# V1_0.net
KiCad netlist of a schematic drawn in Altium Designer
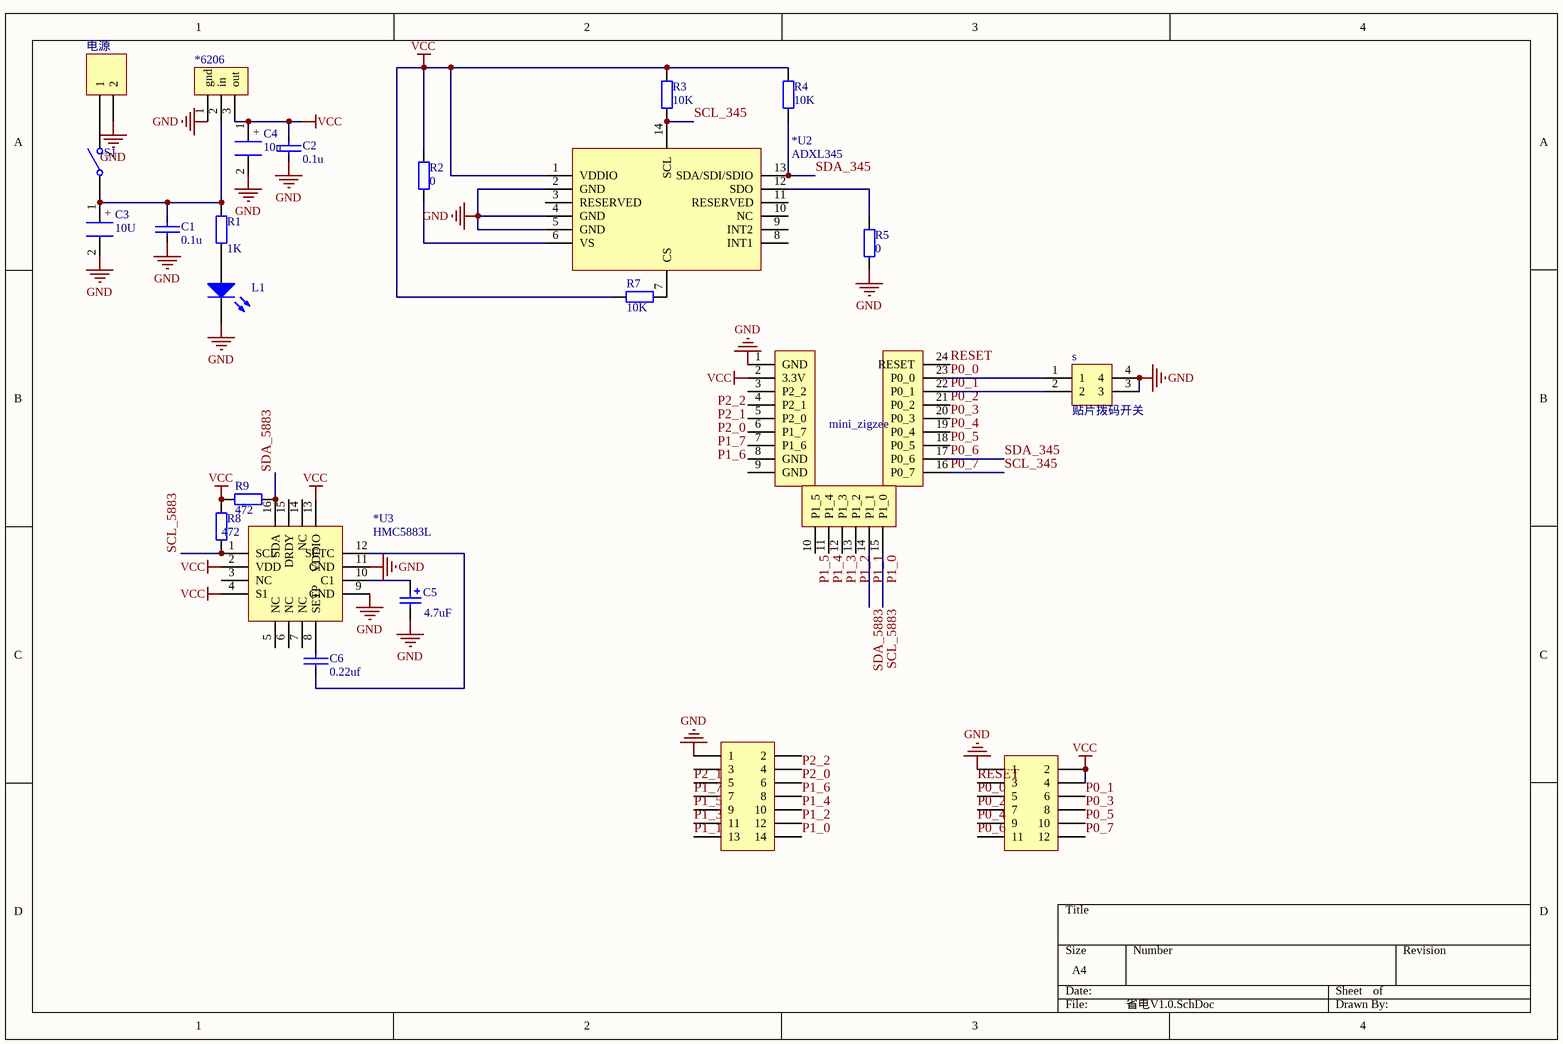
[diagram p0: 省电V1.0.SchDoc]

(export (version "E")
  (design (tool "Eeschema 10.0.6"))
  (components
    (comp (ref "*U1") (value "*6206") (footprint "SOT89/X.7") (libsource (lib "*") (part "6206A")))
    (comp (ref "*U2") (value "ADXL345") (footprint "ADXL345") (libsource (lib "Schlib1") (part "ADXL345")))
    (comp (ref "*U3") (value "HMC5883L") (footprint "HMC5883L") (libsource (lib "*") (part "HMC5883L")))
    (comp (ref "*U4")
      (value "mini_zigzee")
      (footprint "mini_zigbee")
      (libsource (lib "*") (part "mini_zigzee"))
    )
    (comp (ref "C1") (value "0.1u") (footprint "0603") (libsource (lib "hecheng") (part "CAP")))
    (comp (ref "C2") (value "0.1u") (footprint "0603") (libsource (lib "hecheng") (part "CAP")))
    (comp (ref "C3") (value "10U") (footprint "1206") (libsource (lib "hecheng") (part "CAP-10U-T")))
    (comp (ref "C4") (value "10u") (footprint "1206") (libsource (lib "hecheng") (part "CAP-10U-T")))
    (comp (ref "C5")
      (value "4.7uF")
      (footprint "0603")
      (description "Polarized Capacitor (Axial)")
      (fields
        (field (name "MANUFACTURER") "Generic Components")
        (field (name "Comment") "Cap Pol2")
        (field (name "PUBLISHER") "Altium Hobart Technology Centre")
      )
      (libsource (lib "hecheng") (part "Cap Pol2"))
    )
    (comp (ref "C6") (value "0.22uf") (footprint "0603") (libsource (lib "hecheng") (part "CAP")))
    (comp (ref "JP2")
      (value "Header 2X7")
      (footprint "HDR2-7")
      (description "Header, 7-Pin, Dual row")
      (fields (field (name "MANUFACTURER") "Generic Components"))
      (libsource (lib "hecheng") (part "Header 2X7"))
    )
    (comp (ref "JP3")
      (value "Header 2X6")
      (footprint "HDR2-6")
      (description "Header, 6-Pin, Dual row")
      (fields (field (name "MANUFACTURER") "Generic Components"))
      (libsource (lib "hecheng") (part "Header 2X6"))
    )
    (comp (ref "L1") (value "LED-3MM") (footprint "0603") (libsource (lib "hecheng") (part "LED-3MM")))
    (comp (ref "R1")
      (value "1K")
      (footprint "0603")
      (description "Resistor")
      (fields
        (field (name "MANUFACTURER") "Generic Components")
        (field (name "Comment") "Res")
        (field (name "PUBLISHER") "Altium Hobart Technology Centre")
      )
      (libsource (lib "hecheng") (part "Res"))
    )
    (comp (ref "R2")
      (value "0")
      (footprint "0603")
      (description "Resistor")
      (fields
        (field (name "MANUFACTURER") "Generic Components")
        (field (name "Comment") "Res")
        (field (name "PUBLISHER") "Altium Hobart Technology Centre")
      )
      (libsource (lib "hecheng") (part "Res"))
    )
    (comp (ref "R3")
      (value "10K")
      (footprint "0603")
      (description "Resistor")
      (fields
        (field (name "MANUFACTURER") "Generic Components")
        (field (name "Comment") "Res")
        (field (name "PUBLISHER") "Altium Hobart Technology Centre")
      )
      (libsource (lib "hecheng") (part "Res"))
    )
    (comp (ref "R4")
      (value "10K")
      (footprint "0603")
      (description "Resistor")
      (fields
        (field (name "MANUFACTURER") "Generic Components")
        (field (name "Comment") "Res")
        (field (name "PUBLISHER") "Altium Hobart Technology Centre")
      )
      (libsource (lib "hecheng") (part "Res"))
    )
    (comp (ref "R5")
      (value "0")
      (footprint "0603")
      (description "Resistor")
      (fields
        (field (name "MANUFACTURER") "Generic Components")
        (field (name "Comment") "Res")
        (field (name "PUBLISHER") "Altium Hobart Technology Centre")
      )
      (libsource (lib "hecheng") (part "Res"))
    )
    (comp (ref "R7")
      (value "10K")
      (footprint "0603")
      (description "Resistor")
      (fields
        (field (name "MANUFACTURER") "Generic Components")
        (field (name "Comment") "Res")
        (field (name "PUBLISHER") "Altium Hobart Technology Centre")
      )
      (libsource (lib "") (part "Res_1"))
    )
    (comp (ref "R8")
      (value "472")
      (footprint "0603")
      (description "Resistor")
      (fields
        (field (name "MANUFACTURER") "Generic Components")
        (field (name "Comment") "Res")
        (field (name "PUBLISHER") "Altium Hobart Technology Centre")
      )
      (libsource (lib "hecheng") (part "Res"))
    )
    (comp (ref "R9")
      (value "472")
      (footprint "0603")
      (description "Resistor")
      (fields
        (field (name "MANUFACTURER") "Generic Components")
        (field (name "Comment") "Res")
        (field (name "PUBLISHER") "Altium Hobart Technology Centre")
      )
      (libsource (lib "") (part "Res_1"))
    )
    (comp (ref "s") (value "贴片拨码开关") (footprint "贴片拨码开关") (libsource (lib "*") (part "贴片拨码开关")))
    (comp (ref "S1")
      (value "~")
      (footprint "手电筒开关")
      (description "Single-Pole, Single-Throw Switch")
      (fields (field (name "MANUFACTURER") "Generic Components"))
      (libsource (lib "hecheng") (part "SW-SPST"))
    )
    (comp (ref "电源")
      (value "Header 2")
      (footprint "2032纽扣底座")
      (description "Header, 2-Pin")
      (fields (field (name "PUBLISHER") "Altium Limited"))
      (libsource (lib "hecheng") (part "Header 2"))
    )
  )
  (nets
    (net (code "1") (name "/P0_0") (class "Default")
      (node (ref "*U4") (pin "23") (pinfunction "P0_0_23") (pintype "passive"))
      (node (ref "JP3") (pin "5") (pinfunction "5_5") (pintype "passive"))
      (node (ref "s") (pin "1") (pinfunction "1_1") (pintype "passive"))
    )
    (net (code "2") (name "/P0_1") (class "Default")
      (node (ref "*U4") (pin "22") (pinfunction "P0_1_22") (pintype "passive"))
      (node (ref "JP3") (pin "6") (pinfunction "6_6") (pintype "passive"))
      (node (ref "s") (pin "2") (pinfunction "2_2") (pintype "passive"))
    )
    (net (code "3") (name "/P0_2") (class "Default")
      (node (ref "*U4") (pin "21") (pinfunction "P0_2_21") (pintype "passive"))
      (node (ref "JP3") (pin "7") (pinfunction "7_7") (pintype "passive"))
    )
    (net (code "4") (name "/P0_3") (class "Default")
      (node (ref "*U4") (pin "20") (pinfunction "P0_3_20") (pintype "passive"))
      (node (ref "JP3") (pin "8") (pinfunction "8_8") (pintype "passive"))
    )
    (net (code "5") (name "/P0_4") (class "Default")
      (node (ref "*U4") (pin "19") (pinfunction "P0_4_19") (pintype "passive"))
      (node (ref "JP3") (pin "9") (pinfunction "9_9") (pintype "passive"))
    )
    (net (code "6") (name "/P0_5") (class "Default")
      (node (ref "*U4") (pin "18") (pinfunction "P0_5_18") (pintype "passive"))
      (node (ref "JP3") (pin "10") (pinfunction "10_10") (pintype "passive"))
    )
    (net (code "7") (name "/P0_6") (class "Default")
      (node (ref "*U2") (pin "13") (pinfunction "SDA/SDI/SDIO_13") (pintype "passive"))
      (node (ref "*U4") (pin "17") (pinfunction "P0_6_17") (pintype "passive"))
      (node (ref "JP3") (pin "11") (pinfunction "11_11") (pintype "passive"))
      (node (ref "R4") (pin "1") (pinfunction "1_1") (pintype "passive"))
    )
    (net (code "8") (name "/P0_7") (class "Default")
      (node (ref "*U2") (pin "14") (pinfunction "SCL_14") (pintype "passive"))
      (node (ref "*U4") (pin "16") (pinfunction "P0_7_16") (pintype "passive"))
      (node (ref "JP3") (pin "12") (pinfunction "12_12") (pintype "passive"))
      (node (ref "R3") (pin "1") (pinfunction "1_1") (pintype "passive"))
    )
    (net (code "9") (name "/P1_0") (class "Default")
      (node (ref "*U3") (pin "1") (pinfunction "SCL_1") (pintype "passive"))
      (node (ref "*U4") (pin "15") (pinfunction "P1_0_15") (pintype "passive"))
      (node (ref "JP2") (pin "14") (pinfunction "14_14") (pintype "passive"))
      (node (ref "R8") (pin "1") (pinfunction "1_1") (pintype "passive"))
    )
    (net (code "10") (name "/P1_1") (class "Default")
      (node (ref "*U3") (pin "16") (pinfunction "SDA_16") (pintype "passive"))
      (node (ref "*U4") (pin "14") (pinfunction "P1_1_14") (pintype "passive"))
      (node (ref "JP2") (pin "13") (pinfunction "13_13") (pintype "passive"))
      (node (ref "R9") (pin "1") (pinfunction "1_1") (pintype "passive"))
    )
    (net (code "11") (name "/P1_2") (class "Default")
      (node (ref "*U4") (pin "13") (pinfunction "P1_2_13") (pintype "passive"))
      (node (ref "JP2") (pin "12") (pinfunction "12_12") (pintype "passive"))
    )
    (net (code "12") (name "/P1_3") (class "Default")
      (node (ref "*U4") (pin "12") (pinfunction "P1_3_12") (pintype "passive"))
      (node (ref "JP2") (pin "11") (pinfunction "11_11") (pintype "passive"))
    )
    (net (code "13") (name "/P1_4") (class "Default")
      (node (ref "*U4") (pin "11") (pinfunction "P1_4_11") (pintype "passive"))
      (node (ref "JP2") (pin "10") (pinfunction "10_10") (pintype "passive"))
    )
    (net (code "14") (name "/P1_5") (class "Default")
      (node (ref "*U4") (pin "10") (pinfunction "P1_5_10") (pintype "passive"))
      (node (ref "JP2") (pin "9") (pinfunction "9_9") (pintype "passive"))
    )
    (net (code "15") (name "/P1_6") (class "Default")
      (node (ref "*U4") (pin "7") (pinfunction "P1_6_7") (pintype "passive"))
      (node (ref "JP2") (pin "8") (pinfunction "8_8") (pintype "passive"))
    )
    (net (code "16") (name "/P1_7") (class "Default")
      (node (ref "*U4") (pin "6") (pinfunction "P1_7_6") (pintype "passive"))
      (node (ref "JP2") (pin "7") (pinfunction "7_7") (pintype "passive"))
    )
    (net (code "17") (name "/P2_0") (class "Default")
      (node (ref "*U4") (pin "5") (pinfunction "P2_0_5") (pintype "passive"))
      (node (ref "JP2") (pin "6") (pinfunction "6_6") (pintype "passive"))
    )
    (net (code "18") (name "/P2_1") (class "Default")
      (node (ref "*U4") (pin "4") (pinfunction "P2_1_4") (pintype "passive"))
      (node (ref "JP2") (pin "5") (pinfunction "5_5") (pintype "passive"))
    )
    (net (code "19") (name "/P2_2") (class "Default")
      (node (ref "*U4") (pin "3") (pinfunction "P2_2_3") (pintype "passive"))
      (node (ref "JP2") (pin "4") (pinfunction "4_4") (pintype "passive"))
    )
    (net (code "20") (name "/RESET") (class "Default")
      (node (ref "*U4") (pin "24") (pinfunction "RESET_24") (pintype "passive"))
      (node (ref "JP3") (pin "3") (pinfunction "3_3") (pintype "passive"))
    )
    (net (code "21") (name "GND") (class "Default")
      (node (ref "*U1") (pin "1") (pinfunction "gnd_1") (pintype "passive"))
      (node (ref "*U2") (pin "2") (pinfunction "GND_2") (pintype "passive"))
      (node (ref "*U2") (pin "4") (pinfunction "GND_4") (pintype "passive"))
      (node (ref "*U2") (pin "5") (pinfunction "GND_5") (pintype "passive"))
      (node (ref "*U3") (pin "11") (pinfunction "GND_11") (pintype "passive"))
      (node (ref "*U3") (pin "9") (pinfunction "GND_9") (pintype "passive"))
      (node (ref "*U4") (pin "1") (pinfunction "GND_1") (pintype "passive"))
      (node (ref "C1") (pin "2") (pintype "passive"))
      (node (ref "C2") (pin "2") (pintype "passive"))
      (node (ref "C3") (pin "2") (pinfunction "2_2") (pintype "passive"))
      (node (ref "C4") (pin "2") (pinfunction "2_2") (pintype "passive"))
      (node (ref "C5") (pin "2") (pinfunction "2_2") (pintype "passive"))
      (node (ref "JP2") (pin "1") (pinfunction "1_1") (pintype "passive"))
      (node (ref "JP3") (pin "1") (pinfunction "1_1") (pintype "passive"))
      (node (ref "L1") (pin "2") (pinfunction "K_2") (pintype "passive"))
      (node (ref "R5") (pin "1") (pinfunction "1_1") (pintype "passive"))
      (node (ref "s") (pin "3") (pinfunction "3_3") (pintype "passive"))
      (node (ref "s") (pin "4") (pinfunction "4_4") (pintype "passive"))
      (node (ref "电源") (pin "2") (pinfunction "2_2") (pintype "passive"))
    )
    (net (code "22") (name "Net-(*U1-in)") (class "Default")
      (node (ref "*U1") (pin "2") (pinfunction "in_2") (pintype "passive"))
      (node (ref "C1") (pin "1") (pintype "passive"))
      (node (ref "C3") (pin "1") (pinfunction "1_1") (pintype "passive"))
      (node (ref "R1") (pin "2") (pinfunction "2_2") (pintype "passive"))
      (node (ref "S1") (pin "1") (pinfunction "COMMON_1") (pintype "passive"))
    )
    (net (code "23") (name "Net-(*U2-CS)") (class "Default")
      (node (ref "*U2") (pin "7") (pinfunction "CS_7") (pintype "passive"))
      (node (ref "R7") (pin "1") (pinfunction "1_1") (pintype "passive"))
    )
    (net (code "24") (name "Net-(*U2-SDO)") (class "Default")
      (node (ref "*U2") (pin "12") (pinfunction "SDO_12") (pintype "passive"))
      (node (ref "R5") (pin "2") (pinfunction "2_2") (pintype "passive"))
    )
    (net (code "25") (name "Net-(*U2-VS)") (class "Default")
      (node (ref "*U2") (pin "6") (pinfunction "VS_6") (pintype "passive"))
      (node (ref "R2") (pin "1") (pinfunction "1_1") (pintype "passive"))
    )
    (net (code "26") (name "Net-(*U3-C1)") (class "Default")
      (node (ref "*U3") (pin "10") (pinfunction "C1_10") (pintype "passive"))
      (node (ref "C5") (pin "1") (pinfunction "1_1") (pintype "passive"))
    )
    (net (code "27") (name "Net-(*U3-SETC)") (class "Default")
      (node (ref "*U3") (pin "12") (pinfunction "SETC_12") (pintype "passive"))
      (node (ref "C6") (pin "2") (pintype "passive"))
    )
    (net (code "28") (name "Net-(*U3-SETP)") (class "Default")
      (node (ref "*U3") (pin "8") (pinfunction "SETP_8") (pintype "passive"))
      (node (ref "C6") (pin "1") (pintype "passive"))
    )
    (net (code "29") (name "Net-(L1-A)") (class "Default")
      (node (ref "L1") (pin "1") (pinfunction "A_1") (pintype "passive"))
      (node (ref "R1") (pin "1") (pinfunction "1_1") (pintype "passive"))
    )
    (net (code "30") (name "Net-(S1-NO)") (class "Default")
      (node (ref "S1") (pin "2") (pinfunction "NO_2") (pintype "passive"))
      (node (ref "电源") (pin "1") (pinfunction "1_1") (pintype "passive"))
    )
    (net (code "31") (name "VCC") (class "Default")
      (node (ref "*U1") (pin "3") (pinfunction "out_3") (pintype "passive"))
      (node (ref "*U2") (pin "1") (pinfunction "VDDIO_1") (pintype "passive"))
      (node (ref "*U3") (pin "13") (pinfunction "VDDIO_13") (pintype "passive"))
      (node (ref "*U3") (pin "2") (pinfunction "VDD_2") (pintype "passive"))
      (node (ref "*U3") (pin "4") (pinfunction "S1_4") (pintype "passive"))
      (node (ref "*U4") (pin "2") (pinfunction "3.3V_2") (pintype "passive"))
      (node (ref "C2") (pin "1") (pintype "passive"))
      (node (ref "C4") (pin "1") (pinfunction "1_1") (pintype "passive"))
      (node (ref "JP3") (pin "2") (pinfunction "2_2") (pintype "passive"))
      (node (ref "JP3") (pin "4") (pinfunction "4_4") (pintype "passive"))
      (node (ref "R2") (pin "2") (pinfunction "2_2") (pintype "passive"))
      (node (ref "R3") (pin "2") (pinfunction "2_2") (pintype "passive"))
      (node (ref "R4") (pin "2") (pinfunction "2_2") (pintype "passive"))
      (node (ref "R7") (pin "2") (pinfunction "2_2") (pintype "passive"))
      (node (ref "R8") (pin "2") (pinfunction "2_2") (pintype "passive"))
      (node (ref "R9") (pin "2") (pinfunction "2_2") (pintype "passive"))
    )
    (net (code "32") (name "unconnected-(*U2-INT1-Pad8)") (class "Default")
      (node (ref "*U2") (pin "8") (pinfunction "INT1_8") (pintype "passive"))
    )
    (net (code "33") (name "unconnected-(*U2-INT2-Pad9)") (class "Default")
      (node (ref "*U2") (pin "9") (pinfunction "INT2_9") (pintype "passive"))
    )
    (net (code "34") (name "unconnected-(*U2-NC-Pad10)") (class "Default")
      (node (ref "*U2") (pin "10") (pinfunction "NC_10") (pintype "passive"))
    )
    (net (code "35") (name "unconnected-(*U2-RESERVED-Pad3)") (class "Default")
      (node (ref "*U2") (pin "3") (pinfunction "RESERVED_3") (pintype "passive"))
    )
    (net (code "36") (name "unconnected-(*U2-RESERVED-Pad11)") (class "Default")
      (node (ref "*U2") (pin "11") (pinfunction "RESERVED_11") (pintype "passive"))
    )
    (net (code "37") (name "unconnected-(*U3-DRDY-Pad15)") (class "Default")
      (node (ref "*U3") (pin "15") (pinfunction "DRDY_15") (pintype "passive"))
    )
    (net (code "38") (name "unconnected-(*U3-NC-Pad3)") (class "Default")
      (node (ref "*U3") (pin "3") (pinfunction "NC_3") (pintype "passive"))
    )
    (net (code "39") (name "unconnected-(*U3-NC-Pad5)") (class "Default")
      (node (ref "*U3") (pin "5") (pinfunction "NC_5") (pintype "passive"))
    )
    (net (code "40") (name "unconnected-(*U3-NC-Pad6)") (class "Default")
      (node (ref "*U3") (pin "6") (pinfunction "NC_6") (pintype "passive"))
    )
    (net (code "41") (name "unconnected-(*U3-NC-Pad7)") (class "Default")
      (node (ref "*U3") (pin "7") (pinfunction "NC_7") (pintype "passive"))
    )
    (net (code "42") (name "unconnected-(*U3-NC-Pad14)") (class "Default")
      (node (ref "*U3") (pin "14") (pinfunction "NC_14") (pintype "passive"))
    )
    (net (code "43") (name "unconnected-(*U4-GND-Pad8)") (class "Default")
      (node (ref "*U4") (pin "8") (pinfunction "GND_8") (pintype "passive"))
    )
    (net (code "44") (name "unconnected-(*U4-GND-Pad9)") (class "Default")
      (node (ref "*U4") (pin "9") (pinfunction "GND_9") (pintype "passive"))
    )
    (net (code "45") (name "unconnected-(JP2-Pad2)") (class "Default")
      (node (ref "JP2") (pin "2") (pinfunction "2_2") (pintype "passive"))
    )
    (net (code "46") (name "unconnected-(JP2-Pad3)") (class "Default")
      (node (ref "JP2") (pin "3") (pinfunction "3_3") (pintype "passive"))
    )
  )
)
